# owl-digital-2.net
KiCad netlist of a schematic drawn in EAGLE
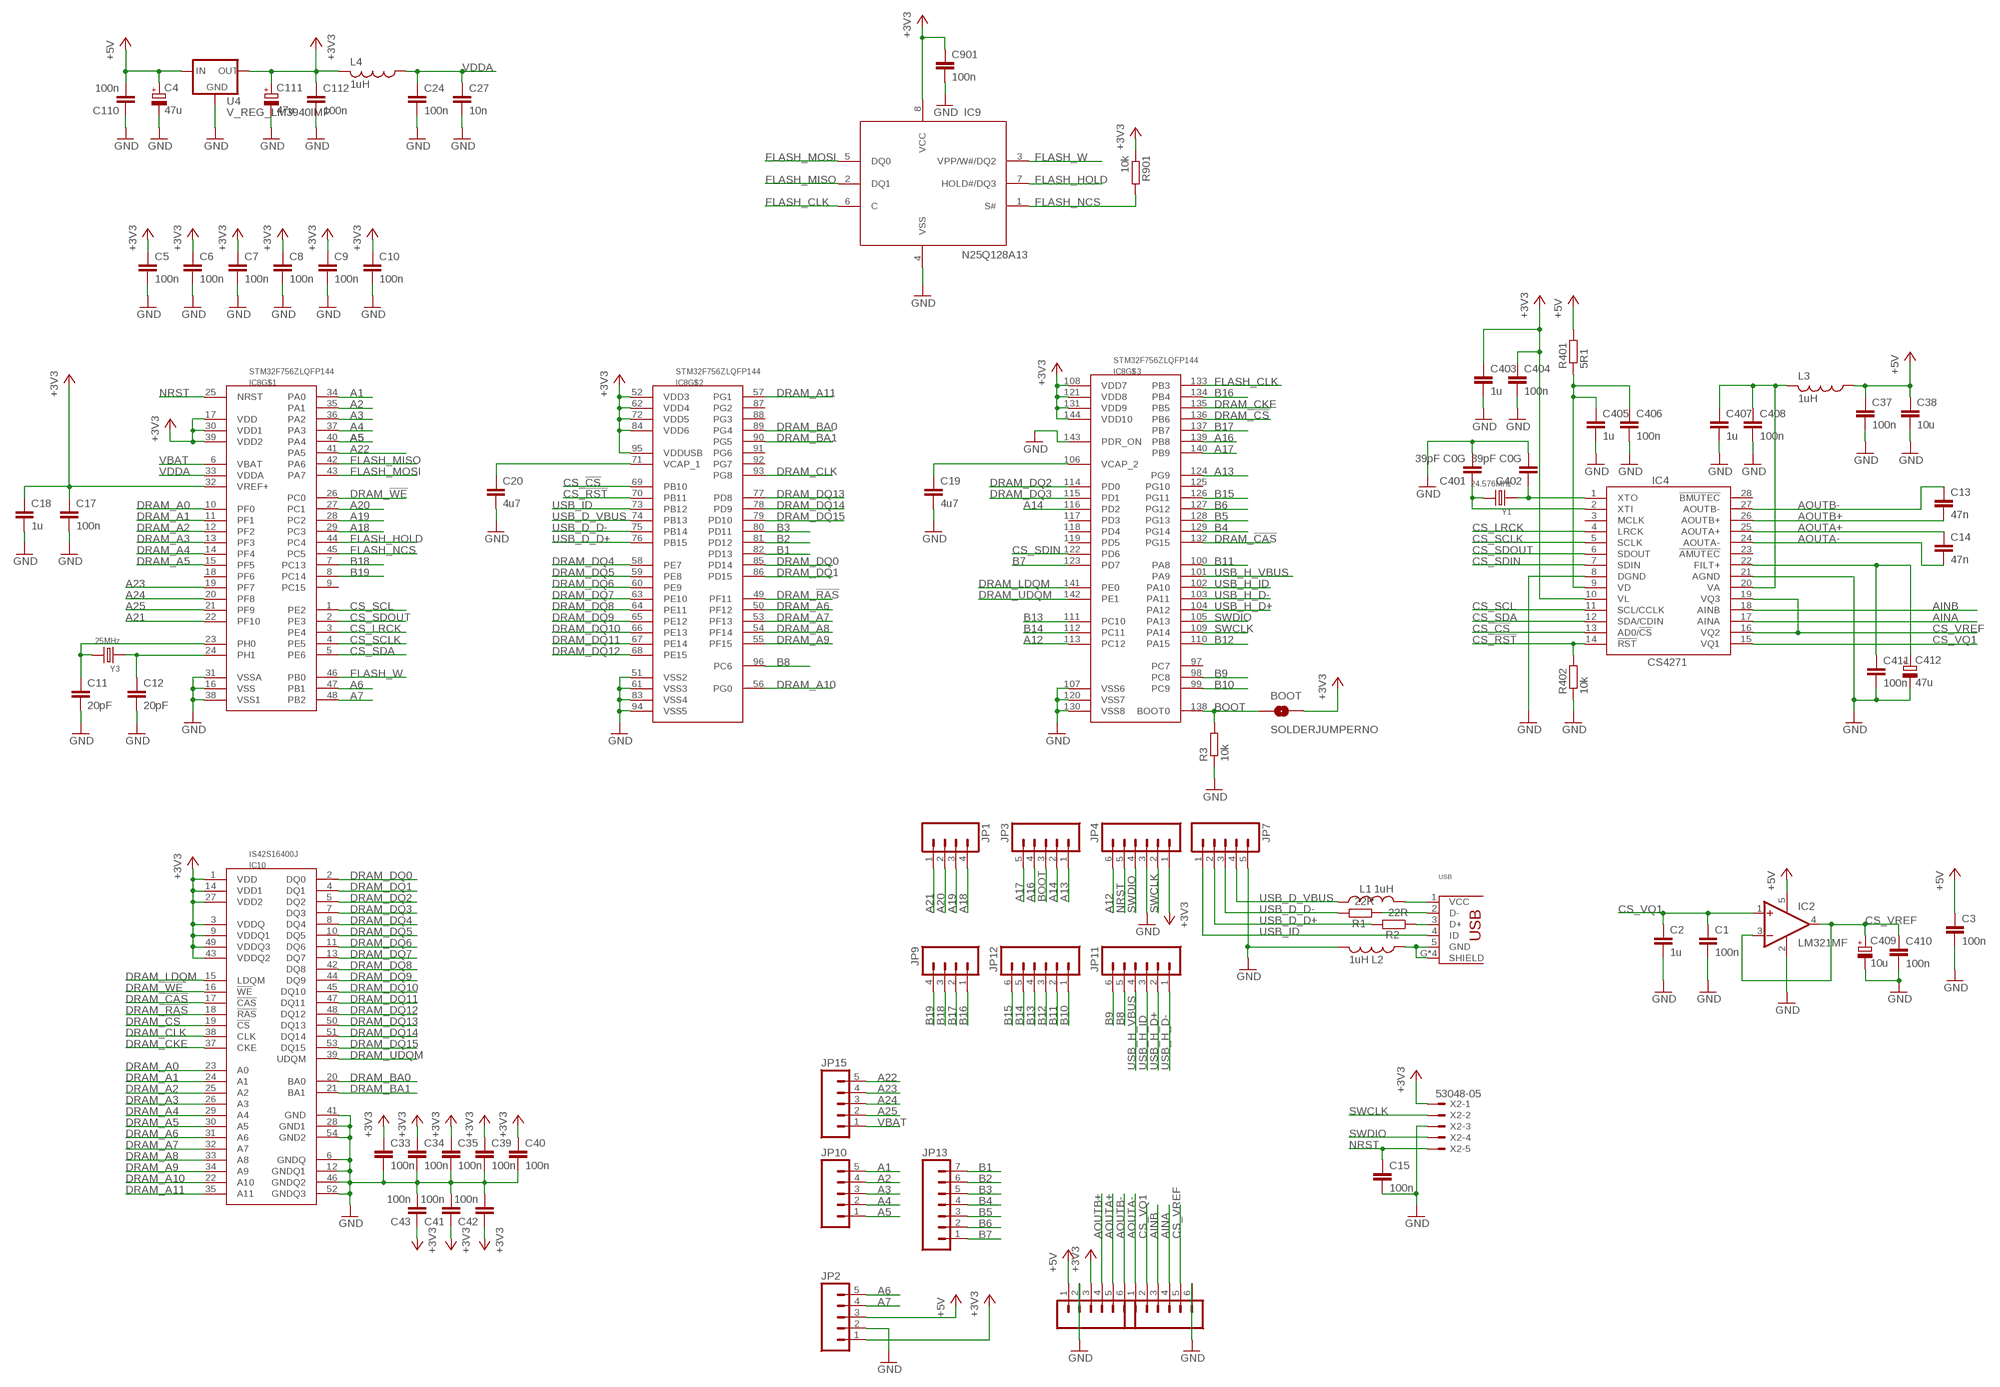
[diagram p0: schematic, sheet 1]

(export (version "E")
  (design (tool "Eeschema 10.0.6"))
  (components
    (comp (ref "BOOT")
      (value "SOLDERJUMPERNO")
      (footprint "eagle-import:SJ_2S-NO")
      (libsource (lib "eagle-import") (part "SOLDERJUMPERNO"))
    )
    (comp (ref "C1")
      (value "100n")
      (footprint "eagle-import:C0603")
      (libsource (lib "eagle-import") (part "C-EUC0603"))
    )
    (comp (ref "C2")
      (value "1u")
      (footprint "eagle-import:C0603")
      (libsource (lib "eagle-import") (part "C-EUC0603"))
    )
    (comp (ref "C3")
      (value "100n")
      (footprint "eagle-import:C0603")
      (libsource (lib "eagle-import") (part "C-EUC0603"))
    )
    (comp (ref "C4")
      (value "47u")
      (footprint "eagle-import:CPOL-5")
      (libsource (lib "eagle-import") (part "CPOL-EU153CLV-0505"))
    )
    (comp (ref "C5")
      (value "100n")
      (footprint "eagle-import:C0603")
      (libsource (lib "eagle-import") (part "C-EUC0603"))
    )
    (comp (ref "C6")
      (value "100n")
      (footprint "eagle-import:C0603")
      (libsource (lib "eagle-import") (part "C-EUC0603"))
    )
    (comp (ref "C7")
      (value "100n")
      (footprint "eagle-import:C0603")
      (libsource (lib "eagle-import") (part "C-EUC0603"))
    )
    (comp (ref "C8")
      (value "100n")
      (footprint "eagle-import:C0603")
      (libsource (lib "eagle-import") (part "C-EUC0603"))
    )
    (comp (ref "C9")
      (value "100n")
      (footprint "eagle-import:C0603")
      (libsource (lib "eagle-import") (part "C-EUC0603"))
    )
    (comp (ref "C10")
      (value "100n")
      (footprint "eagle-import:C0603")
      (libsource (lib "eagle-import") (part "C-EUC0603"))
    )
    (comp (ref "C11")
      (value "20pF")
      (footprint "eagle-import:C0603")
      (libsource (lib "eagle-import") (part "C-EUC0603"))
    )
    (comp (ref "C12")
      (value "20pF")
      (footprint "eagle-import:C0603")
      (libsource (lib "eagle-import") (part "C-EUC0603"))
    )
    (comp (ref "C13")
      (value "47n")
      (footprint "eagle-import:C0603")
      (libsource (lib "eagle-import") (part "C-EUC0603"))
    )
    (comp (ref "C14")
      (value "47n")
      (footprint "eagle-import:C0603")
      (libsource (lib "eagle-import") (part "C-EUC0603"))
    )
    (comp (ref "C15")
      (value "100n")
      (footprint "eagle-import:C0603")
      (libsource (lib "eagle-import") (part "C-EUC0603"))
    )
    (comp (ref "C17")
      (value "100n")
      (footprint "eagle-import:C0603")
      (libsource (lib "eagle-import") (part "C-EUC0603"))
    )
    (comp (ref "C18")
      (value "1u")
      (footprint "eagle-import:C0603")
      (libsource (lib "eagle-import") (part "C-EUC0603"))
    )
    (comp (ref "C19")
      (value "4u7")
      (footprint "eagle-import:C0603")
      (libsource (lib "eagle-import") (part "C-EUC0603"))
    )
    (comp (ref "C20")
      (value "4u7")
      (footprint "eagle-import:C0603")
      (libsource (lib "eagle-import") (part "C-EUC0603"))
    )
    (comp (ref "C24")
      (value "100n")
      (footprint "eagle-import:C0603")
      (libsource (lib "eagle-import") (part "C-EUC0603"))
    )
    (comp (ref "C27")
      (value "10n")
      (footprint "eagle-import:C0603")
      (libsource (lib "eagle-import") (part "C-EUC0603"))
    )
    (comp (ref "C33")
      (value "100n")
      (footprint "eagle-import:C0603")
      (libsource (lib "eagle-import") (part "C-EUC0603"))
    )
    (comp (ref "C34")
      (value "100n")
      (footprint "eagle-import:C0603")
      (libsource (lib "eagle-import") (part "C-EUC0603"))
    )
    (comp (ref "C35")
      (value "100n")
      (footprint "eagle-import:C0603")
      (libsource (lib "eagle-import") (part "C-EUC0603"))
    )
    (comp (ref "C37")
      (value "100n")
      (footprint "eagle-import:C0603")
      (libsource (lib "eagle-import") (part "C-EUC0603"))
    )
    (comp (ref "C38")
      (value "10u")
      (footprint "eagle-import:C1206")
      (libsource (lib "eagle-import") (part "C-EUC1206"))
    )
    (comp (ref "C39")
      (value "100n")
      (footprint "eagle-import:C0603")
      (libsource (lib "eagle-import") (part "C-EUC0603"))
    )
    (comp (ref "C40")
      (value "100n")
      (footprint "eagle-import:C0603")
      (libsource (lib "eagle-import") (part "C-EUC0603"))
    )
    (comp (ref "C41")
      (value "100n")
      (footprint "eagle-import:C0603")
      (libsource (lib "eagle-import") (part "C-EUC0603"))
    )
    (comp (ref "C42")
      (value "100n")
      (footprint "eagle-import:C0603")
      (libsource (lib "eagle-import") (part "C-EUC0603"))
    )
    (comp (ref "C43")
      (value "100n")
      (footprint "eagle-import:C0603")
      (libsource (lib "eagle-import") (part "C-EUC0603"))
    )
    (comp (ref "C110")
      (value "100n")
      (footprint "eagle-import:C0603")
      (libsource (lib "eagle-import") (part "C-EUC0603"))
    )
    (comp (ref "C111")
      (value "47u")
      (footprint "eagle-import:CPOL-5")
      (libsource (lib "eagle-import") (part "CPOL-EU153CLV-0505"))
    )
    (comp (ref "C112")
      (value "100n")
      (footprint "eagle-import:C0603")
      (libsource (lib "eagle-import") (part "C-EUC0603"))
    )
    (comp (ref "C401")
      (value "39pF C0G")
      (footprint "eagle-import:C0603")
      (libsource (lib "eagle-import") (part "C-EUC0603"))
    )
    (comp (ref "C402")
      (value "39pF C0G")
      (footprint "eagle-import:C0603")
      (libsource (lib "eagle-import") (part "C-EUC0603"))
    )
    (comp (ref "C403")
      (value "1u")
      (footprint "eagle-import:C0603")
      (libsource (lib "eagle-import") (part "C-EUC0603"))
    )
    (comp (ref "C404")
      (value "100n")
      (footprint "eagle-import:C0603")
      (libsource (lib "eagle-import") (part "C-EUC0603"))
    )
    (comp (ref "C405")
      (value "1u")
      (footprint "eagle-import:C0603")
      (libsource (lib "eagle-import") (part "C-EUC0603"))
    )
    (comp (ref "C406")
      (value "100n")
      (footprint "eagle-import:C0603")
      (libsource (lib "eagle-import") (part "C-EUC0603"))
    )
    (comp (ref "C407")
      (value "1u")
      (footprint "eagle-import:C0603")
      (libsource (lib "eagle-import") (part "C-EUC0603"))
    )
    (comp (ref "C408")
      (value "100n")
      (footprint "eagle-import:C0603")
      (libsource (lib "eagle-import") (part "C-EUC0603"))
    )
    (comp (ref "C409")
      (value "10u")
      (footprint "eagle-import:CPOL-5")
      (libsource (lib "eagle-import") (part "CPOL-EU153CLV-0505"))
    )
    (comp (ref "C410")
      (value "100n")
      (footprint "eagle-import:C0603")
      (libsource (lib "eagle-import") (part "C-EUC0603"))
    )
    (comp (ref "C411")
      (value "100n")
      (footprint "eagle-import:C0603")
      (libsource (lib "eagle-import") (part "C-EUC0603"))
    )
    (comp (ref "C412")
      (value "47u")
      (footprint "eagle-import:CPOL-5")
      (libsource (lib "eagle-import") (part "CPOL-EU153CLV-0505"))
    )
    (comp (ref "C901")
      (value "100n")
      (footprint "eagle-import:C0603")
      (libsource (lib "eagle-import") (part "C-EUC0603"))
    )
    (comp (ref "IC2")
      (value "LM321MF")
      (footprint "eagle-import:SOT23-5")
      (libsource (lib "eagle-import") (part "LM321?MF"))
    )
    (comp (ref "IC4")
      (value "CS4271")
      (footprint "eagle-import:TSSOP28-0.65-9.7X4.4MM")
      (libsource (lib "eagle-import") (part "CS4271"))
    )
    (comp (ref "IC8")
      (value "STM32F756ZLQFP144")
      (footprint "eagle-import:QFP50P2200X2200X160-144N")
      (fields (field (name "OC_FARNELL") "2484975"))
      (libsource (lib "eagle-import") (part "STM32F756ZLQFP144"))
    )
    (comp (ref "IC9")
      (value "N25Q128A13")
      (footprint "eagle-import:SO8W")
      (libsource (lib "eagle-import") (part "N25Q128A13"))
    )
    (comp (ref "IC10")
      (value "IS42S16400J")
      (footprint "eagle-import:TSOP54-400")
      (libsource (lib "eagle-import") (part "IS42S16400J"))
    )
    (comp (ref "JP1")
      (value "M04PTH")
      (footprint "eagle-import:1X04")
      (libsource (lib "eagle-import") (part "M04PTH"))
    )
    (comp (ref "JP2")
      (value "M05PTH")
      (footprint "eagle-import:1X05")
      (libsource (lib "eagle-import") (part "M05PTH"))
    )
    (comp (ref "JP3")
      (value "M05PTH")
      (footprint "eagle-import:1X05")
      (libsource (lib "eagle-import") (part "M05PTH"))
    )
    (comp (ref "JP4")
      (value "M06SIP")
      (footprint "eagle-import:1X06")
      (libsource (lib "eagle-import") (part "M06SIP"))
    )
    (comp (ref "JP5")
      (value "M06SIP")
      (footprint "eagle-import:1X06")
      (libsource (lib "eagle-import") (part "M06SIP"))
    )
    (comp (ref "JP6")
      (value "M06SIP")
      (footprint "eagle-import:1X06")
      (libsource (lib "eagle-import") (part "M06SIP"))
    )
    (comp (ref "JP7")
      (value "M05PTH")
      (footprint "eagle-import:1X05")
      (libsource (lib "eagle-import") (part "M05PTH"))
    )
    (comp (ref "JP9")
      (value "M04PTH")
      (footprint "eagle-import:1X04")
      (libsource (lib "eagle-import") (part "M04PTH"))
    )
    (comp (ref "JP10")
      (value "M05PTH")
      (footprint "eagle-import:1X05")
      (libsource (lib "eagle-import") (part "M05PTH"))
    )
    (comp (ref "JP11")
      (value "M06SIP")
      (footprint "eagle-import:1X06")
      (libsource (lib "eagle-import") (part "M06SIP"))
    )
    (comp (ref "JP12")
      (value "M06SIP")
      (footprint "eagle-import:1X06")
      (libsource (lib "eagle-import") (part "M06SIP"))
    )
    (comp (ref "JP13")
      (value "M07")
      (footprint "eagle-import:1X07")
      (libsource (lib "eagle-import") (part "M07"))
    )
    (comp (ref "JP15")
      (value "M05PTH")
      (footprint "eagle-import:1X05")
      (libsource (lib "eagle-import") (part "M05PTH"))
    )
    (comp (ref "L1")
      (value "1uH")
      (footprint "eagle-import:0603")
      (libsource (lib "eagle-import") (part "INDUCTOR"))
    )
    (comp (ref "L2")
      (value "1uH")
      (footprint "eagle-import:0603")
      (libsource (lib "eagle-import") (part "INDUCTOR"))
    )
    (comp (ref "L3")
      (value "1uH")
      (footprint "eagle-import:0603")
      (libsource (lib "eagle-import") (part "INDUCTOR"))
    )
    (comp (ref "L4")
      (value "1uH")
      (footprint "eagle-import:0603")
      (libsource (lib "eagle-import") (part "INDUCTOR"))
    )
    (comp (ref "R1")
      (value "22R")
      (footprint "eagle-import:0603")
      (libsource (lib "eagle-import") (part "R-EU_0603"))
    )
    (comp (ref "R2")
      (value "22R")
      (footprint "eagle-import:0603")
      (libsource (lib "eagle-import") (part "R-EU_0603"))
    )
    (comp (ref "R3")
      (value "10k")
      (footprint "eagle-import:0603")
      (libsource (lib "eagle-import") (part "R-EU_0603"))
    )
    (comp (ref "R401")
      (value "5R1")
      (footprint "eagle-import:0603")
      (libsource (lib "eagle-import") (part "R-EU_0603"))
    )
    (comp (ref "R402")
      (value "10k")
      (footprint "eagle-import:0603")
      (libsource (lib "eagle-import") (part "R-EU_0603"))
    )
    (comp (ref "R901")
      (value "10k")
      (footprint "eagle-import:0603")
      (libsource (lib "eagle-import") (part "R-EU_0603"))
    )
    (comp (ref "U4")
      (value "V_REG_LM3940IMP")
      (footprint "eagle-import:SOT223")
      (libsource (lib "eagle-import") (part "V_REG_LM3940IMP"))
    )
    (comp (ref "USB")
      (value "USB_HRS_ZX62-B-5PA(11)MICRO.B")
      (footprint "eagle-import:HRS_ZX62RD-AB-5P8")
      (libsource (lib "eagle-import") (part "USB_HRS_ZX62-B-5PA(11)MICRO.B"))
    )
    (comp (ref "X2")
      (value "53048-05")
      (footprint "eagle-import:53048-05")
      (fields (field (name "MF") "MOLEX") (field (name "MPN") "53048-0510"))
      (libsource (lib "eagle-import") (part "53?-05048"))
    )
    (comp (ref "Y1")
      (value "24.576MHz")
      (footprint "eagle-import:X2-SMD-5.0X3.2X1.3MM")
      (fields (field (name "MPN") "5032/2P"))
      (libsource (lib "eagle-import") (part "SMD-CRYSTAL-8MHZ-20PF-20PPM(2P-5.0X3.2MM)"))
    )
    (comp (ref "Y3")
      (value "25MHz")
      (footprint "eagle-import:X2-SMD-5.0X3.2X1.3MM")
      (fields (field (name "MPN") "5032/2P"))
      (libsource (lib "eagle-import") (part "SMD-CRYSTAL-8MHZ-20PF-20PPM(2P-5.0X3.2MM)"))
    )
  )
  (nets
    (net (code "1") (name "+3V3") (class "Default")
      (node (ref "BOOT") (pin "2") (pinfunction "2_2") (pintype "passive"))
      (node (ref "C10") (pin "1") (pinfunction "1_1") (pintype "passive"))
      (node (ref "C111") (pin "+") (pinfunction "+_+") (pintype "passive"))
      (node (ref "C112") (pin "1") (pinfunction "1_1") (pintype "passive"))
      (node (ref "C17") (pin "1") (pinfunction "1_1") (pintype "passive"))
      (node (ref "C18") (pin "1") (pinfunction "1_1") (pintype "passive"))
      (node (ref "C33") (pin "1") (pinfunction "1_1") (pintype "passive"))
      (node (ref "C34") (pin "1") (pinfunction "1_1") (pintype "passive"))
      (node (ref "C35") (pin "1") (pinfunction "1_1") (pintype "passive"))
      (node (ref "C39") (pin "1") (pinfunction "1_1") (pintype "passive"))
      (node (ref "C40") (pin "1") (pinfunction "1_1") (pintype "passive"))
      (node (ref "C403") (pin "1") (pinfunction "1_1") (pintype "passive"))
      (node (ref "C404") (pin "1") (pinfunction "1_1") (pintype "passive"))
      (node (ref "C41") (pin "1") (pinfunction "1_1") (pintype "passive"))
      (node (ref "C42") (pin "1") (pinfunction "1_1") (pintype "passive"))
      (node (ref "C43") (pin "1") (pinfunction "1_1") (pintype "passive"))
      (node (ref "C5") (pin "1") (pinfunction "1_1") (pintype "passive"))
      (node (ref "C6") (pin "1") (pinfunction "1_1") (pintype "passive"))
      (node (ref "C7") (pin "1") (pinfunction "1_1") (pintype "passive"))
      (node (ref "C8") (pin "1") (pinfunction "1_1") (pintype "passive"))
      (node (ref "C9") (pin "1") (pinfunction "1_1") (pintype "passive"))
      (node (ref "C901") (pin "1") (pinfunction "1_1") (pintype "passive"))
      (node (ref "IC10") (pin "1") (pinfunction "VDD_1") (pintype "bidirectional"))
      (node (ref "IC10") (pin "14") (pinfunction "VDD1_14") (pintype "bidirectional"))
      (node (ref "IC10") (pin "27") (pinfunction "VDD2_27") (pintype "bidirectional"))
      (node (ref "IC10") (pin "3") (pinfunction "VDDQ_3") (pintype "bidirectional"))
      (node (ref "IC10") (pin "43") (pinfunction "VDDQ2_43") (pintype "bidirectional"))
      (node (ref "IC10") (pin "49") (pinfunction "VDDQ3_49") (pintype "bidirectional"))
      (node (ref "IC10") (pin "9") (pinfunction "VDDQ1_9") (pintype "bidirectional"))
      (node (ref "IC4") (pin "10") (pinfunction "VL_10") (pintype "bidirectional"))
      (node (ref "IC8") (pin "108") (pinfunction "VDD7_108") (pintype "bidirectional"))
      (node (ref "IC8") (pin "121") (pinfunction "VDD8_121") (pintype "bidirectional"))
      (node (ref "IC8") (pin "131") (pinfunction "VDD9_131") (pintype "bidirectional"))
      (node (ref "IC8") (pin "144") (pinfunction "VDD10_144") (pintype "bidirectional"))
      (node (ref "IC8") (pin "17") (pinfunction "VDD_17") (pintype "bidirectional"))
      (node (ref "IC8") (pin "30") (pinfunction "VDD1_30") (pintype "bidirectional"))
      (node (ref "IC8") (pin "32") (pinfunction "VREF+_32") (pintype "bidirectional"))
      (node (ref "IC8") (pin "39") (pinfunction "VDD2_39") (pintype "bidirectional"))
      (node (ref "IC8") (pin "52") (pinfunction "VDD3_52") (pintype "bidirectional"))
      (node (ref "IC8") (pin "62") (pinfunction "VDD4_62") (pintype "bidirectional"))
      (node (ref "IC8") (pin "72") (pinfunction "VDD5_72") (pintype "bidirectional"))
      (node (ref "IC8") (pin "84") (pinfunction "VDD6_84") (pintype "bidirectional"))
      (node (ref "IC8") (pin "95") (pinfunction "VDDUSB_95") (pintype "bidirectional"))
      (node (ref "IC9") (pin "8") (pinfunction "VCC_8") (pintype "bidirectional"))
      (node (ref "JP2") (pin "1") (pinfunction "1_1") (pintype "passive"))
      (node (ref "JP4") (pin "1") (pinfunction "1_1") (pintype "passive"))
      (node (ref "JP5") (pin "3") (pinfunction "3_3") (pintype "passive"))
      (node (ref "L4") (pin "2") (pinfunction "2_2") (pintype "passive"))
      (node (ref "R901") (pin "1") (pinfunction "1_1") (pintype "passive"))
      (node (ref "U4") (pin "3") (pinfunction "OUT_3") (pintype "output"))
      (node (ref "X2") (pin "1") (pinfunction "S_1") (pintype "passive"))
    )
    (net (code "2") (name "+5V") (class "Default")
      (node (ref "C110") (pin "2") (pinfunction "2_2") (pintype "passive"))
      (node (ref "C3") (pin "1") (pinfunction "1_1") (pintype "passive"))
      (node (ref "C37") (pin "1") (pinfunction "1_1") (pintype "passive"))
      (node (ref "C38") (pin "1") (pinfunction "1_1") (pintype "passive"))
      (node (ref "C4") (pin "+") (pinfunction "+_+") (pintype "passive"))
      (node (ref "IC2") (pin "5") (pinfunction "V+_5") (pintype "power_in"))
      (node (ref "JP2") (pin "3") (pinfunction "3_3") (pintype "passive"))
      (node (ref "JP5") (pin "1") (pinfunction "1_1") (pintype "passive"))
      (node (ref "L3") (pin "1") (pinfunction "1_1") (pintype "passive"))
      (node (ref "R401") (pin "2") (pinfunction "2_2") (pintype "passive"))
      (node (ref "U4") (pin "1") (pinfunction "IN_1") (pintype "input"))
    )
    (net (code "3") (name "/A1") (class "Default")
      (node (ref "IC8") (pin "34") (pinfunction "PA0_34") (pintype "bidirectional"))
      (node (ref "JP10") (pin "5") (pinfunction "5_5") (pintype "passive"))
    )
    (net (code "4") (name "/A2") (class "Default")
      (node (ref "IC8") (pin "35") (pinfunction "PA1_35") (pintype "bidirectional"))
      (node (ref "JP10") (pin "4") (pinfunction "4_4") (pintype "passive"))
    )
    (net (code "5") (name "/A3") (class "Default")
      (node (ref "IC8") (pin "36") (pinfunction "PA2_36") (pintype "bidirectional"))
      (node (ref "JP10") (pin "3") (pinfunction "3_3") (pintype "passive"))
    )
    (net (code "6") (name "/A4") (class "Default")
      (node (ref "IC8") (pin "37") (pinfunction "PA3_37") (pintype "bidirectional"))
      (node (ref "JP10") (pin "2") (pinfunction "2_2") (pintype "passive"))
    )
    (net (code "7") (name "/A5") (class "Default")
      (node (ref "IC8") (pin "40") (pinfunction "PA4_40") (pintype "bidirectional"))
      (node (ref "JP10") (pin "1") (pinfunction "1_1") (pintype "passive"))
    )
    (net (code "8") (name "/A6") (class "Default")
      (node (ref "IC8") (pin "47") (pinfunction "PB1_47") (pintype "bidirectional"))
      (node (ref "JP2") (pin "5") (pinfunction "5_5") (pintype "passive"))
    )
    (net (code "9") (name "/A7") (class "Default")
      (node (ref "IC8") (pin "48") (pinfunction "PB2_48") (pintype "bidirectional"))
      (node (ref "JP2") (pin "4") (pinfunction "4_4") (pintype "passive"))
    )
    (net (code "10") (name "/A12") (class "Default")
      (node (ref "IC8") (pin "113") (pinfunction "PC12_113") (pintype "bidirectional"))
      (node (ref "JP4") (pin "6") (pinfunction "6_6") (pintype "passive"))
    )
    (net (code "11") (name "/A13") (class "Default")
      (node (ref "IC8") (pin "124") (pinfunction "PG9_124") (pintype "bidirectional"))
      (node (ref "JP3") (pin "1") (pinfunction "1_1") (pintype "passive"))
    )
    (net (code "12") (name "/A14") (class "Default")
      (node (ref "IC8") (pin "116") (pinfunction "PD2_116") (pintype "bidirectional"))
      (node (ref "JP3") (pin "2") (pinfunction "2_2") (pintype "passive"))
    )
    (net (code "13") (name "/A16") (class "Default")
      (node (ref "IC8") (pin "139") (pinfunction "PB8_139") (pintype "bidirectional"))
      (node (ref "JP3") (pin "4") (pinfunction "4_4") (pintype "passive"))
    )
    (net (code "14") (name "/A17") (class "Default")
      (node (ref "IC8") (pin "140") (pinfunction "PB9_140") (pintype "bidirectional"))
      (node (ref "JP3") (pin "5") (pinfunction "5_5") (pintype "passive"))
    )
    (net (code "15") (name "/A18") (class "Default")
      (node (ref "IC8") (pin "29") (pinfunction "PC3_29") (pintype "bidirectional"))
      (node (ref "JP1") (pin "4") (pinfunction "4_4") (pintype "passive"))
    )
    (net (code "16") (name "/A19") (class "Default")
      (node (ref "IC8") (pin "28") (pinfunction "PC2_28") (pintype "bidirectional"))
      (node (ref "JP1") (pin "3") (pinfunction "3_3") (pintype "passive"))
    )
    (net (code "17") (name "/A20") (class "Default")
      (node (ref "IC8") (pin "27") (pinfunction "PC1_27") (pintype "bidirectional"))
      (node (ref "JP1") (pin "2") (pinfunction "2_2") (pintype "passive"))
    )
    (net (code "18") (name "/A21") (class "Default")
      (node (ref "IC8") (pin "22") (pinfunction "PF10_22") (pintype "bidirectional"))
      (node (ref "JP1") (pin "1") (pinfunction "1_1") (pintype "passive"))
    )
    (net (code "19") (name "/A22") (class "Default")
      (node (ref "IC8") (pin "41") (pinfunction "PA5_41") (pintype "bidirectional"))
      (node (ref "JP15") (pin "5") (pinfunction "5_5") (pintype "passive"))
    )
    (net (code "20") (name "/A23") (class "Default")
      (node (ref "IC8") (pin "19") (pinfunction "PF7_19") (pintype "bidirectional"))
      (node (ref "JP15") (pin "4") (pinfunction "4_4") (pintype "passive"))
    )
    (net (code "21") (name "/A24") (class "Default")
      (node (ref "IC8") (pin "20") (pinfunction "PF8_20") (pintype "bidirectional"))
      (node (ref "JP15") (pin "3") (pinfunction "3_3") (pintype "passive"))
    )
    (net (code "22") (name "/A25") (class "Default")
      (node (ref "IC8") (pin "21") (pinfunction "PF9_21") (pintype "bidirectional"))
      (node (ref "JP15") (pin "2") (pinfunction "2_2") (pintype "passive"))
    )
    (net (code "23") (name "/AINA") (class "Default")
      (node (ref "IC4") (pin "17") (pinfunction "AINA_17") (pintype "bidirectional"))
      (node (ref "JP6") (pin "4") (pinfunction "4_4") (pintype "passive"))
    )
    (net (code "24") (name "/AINB") (class "Default")
      (node (ref "IC4") (pin "18") (pinfunction "AINB_18") (pintype "bidirectional"))
      (node (ref "JP6") (pin "3") (pinfunction "3_3") (pintype "passive"))
    )
    (net (code "25") (name "/AOUTA+") (class "Default")
      (node (ref "C14") (pin "1") (pinfunction "1_1") (pintype "passive"))
      (node (ref "IC4") (pin "25") (pinfunction "AOUTA+_25") (pintype "bidirectional"))
      (node (ref "JP5") (pin "5") (pinfunction "5_5") (pintype "passive"))
    )
    (net (code "26") (name "/AOUTA-") (class "Default")
      (node (ref "C14") (pin "2") (pinfunction "2_2") (pintype "passive"))
      (node (ref "IC4") (pin "24") (pinfunction "AOUTA-_24") (pintype "bidirectional"))
      (node (ref "JP6") (pin "1") (pinfunction "1_1") (pintype "passive"))
    )
    (net (code "27") (name "/AOUTB+") (class "Default")
      (node (ref "C13") (pin "2") (pinfunction "2_2") (pintype "passive"))
      (node (ref "IC4") (pin "26") (pinfunction "AOUTB+_26") (pintype "bidirectional"))
      (node (ref "JP5") (pin "4") (pinfunction "4_4") (pintype "passive"))
    )
    (net (code "28") (name "/AOUTB-") (class "Default")
      (node (ref "C13") (pin "1") (pinfunction "1_1") (pintype "passive"))
      (node (ref "IC4") (pin "27") (pinfunction "AOUTB-_27") (pintype "bidirectional"))
      (node (ref "JP5") (pin "6") (pinfunction "6_6") (pintype "passive"))
    )
    (net (code "29") (name "/B1") (class "Default")
      (node (ref "IC8") (pin "82") (pinfunction "PD13_82") (pintype "bidirectional"))
      (node (ref "JP13") (pin "7") (pinfunction "7_7") (pintype "passive"))
    )
    (net (code "30") (name "/B2") (class "Default")
      (node (ref "IC8") (pin "81") (pinfunction "PD12_81") (pintype "bidirectional"))
      (node (ref "JP13") (pin "6") (pinfunction "6_6") (pintype "passive"))
    )
    (net (code "31") (name "/B3") (class "Default")
      (node (ref "IC8") (pin "80") (pinfunction "PD11_80") (pintype "bidirectional"))
      (node (ref "JP13") (pin "5") (pinfunction "5_5") (pintype "passive"))
    )
    (net (code "32") (name "/B4") (class "Default")
      (node (ref "IC8") (pin "129") (pinfunction "PG14_129") (pintype "bidirectional"))
      (node (ref "JP13") (pin "4") (pinfunction "4_4") (pintype "passive"))
    )
    (net (code "33") (name "/B5") (class "Default")
      (node (ref "IC8") (pin "128") (pinfunction "PG13_128") (pintype "bidirectional"))
      (node (ref "JP13") (pin "3") (pinfunction "3_3") (pintype "passive"))
    )
    (net (code "34") (name "/B6") (class "Default")
      (node (ref "IC8") (pin "127") (pinfunction "PG12_127") (pintype "bidirectional"))
      (node (ref "JP13") (pin "2") (pinfunction "2_2") (pintype "passive"))
    )
    (net (code "35") (name "/B7") (class "Default")
      (node (ref "IC8") (pin "123") (pinfunction "PD7_123") (pintype "bidirectional"))
      (node (ref "JP13") (pin "1") (pinfunction "1_1") (pintype "passive"))
    )
    (net (code "36") (name "/B8") (class "Default")
      (node (ref "IC8") (pin "96") (pinfunction "PC6_96") (pintype "bidirectional"))
      (node (ref "JP11") (pin "5") (pinfunction "5_5") (pintype "passive"))
    )
    (net (code "37") (name "/B9") (class "Default")
      (node (ref "IC8") (pin "98") (pinfunction "PC8_98") (pintype "bidirectional"))
      (node (ref "JP11") (pin "6") (pinfunction "6_6") (pintype "passive"))
    )
    (net (code "38") (name "/B10") (class "Default")
      (node (ref "IC8") (pin "99") (pinfunction "PC9_99") (pintype "bidirectional"))
      (node (ref "JP12") (pin "1") (pinfunction "1_1") (pintype "passive"))
    )
    (net (code "39") (name "/B11") (class "Default")
      (node (ref "IC8") (pin "100") (pinfunction "PA8_100") (pintype "bidirectional"))
      (node (ref "JP12") (pin "2") (pinfunction "2_2") (pintype "passive"))
    )
    (net (code "40") (name "/B12") (class "Default")
      (node (ref "IC8") (pin "110") (pinfunction "PA15_110") (pintype "bidirectional"))
      (node (ref "JP12") (pin "3") (pinfunction "3_3") (pintype "passive"))
    )
    (net (code "41") (name "/B13") (class "Default")
      (node (ref "IC8") (pin "111") (pinfunction "PC10_111") (pintype "bidirectional"))
      (node (ref "JP12") (pin "4") (pinfunction "4_4") (pintype "passive"))
    )
    (net (code "42") (name "/B14") (class "Default")
      (node (ref "IC8") (pin "112") (pinfunction "PC11_112") (pintype "bidirectional"))
      (node (ref "JP12") (pin "5") (pinfunction "5_5") (pintype "passive"))
    )
    (net (code "43") (name "/B15") (class "Default")
      (node (ref "IC8") (pin "126") (pinfunction "PG11_126") (pintype "bidirectional"))
      (node (ref "JP12") (pin "6") (pinfunction "6_6") (pintype "passive"))
    )
    (net (code "44") (name "/B16") (class "Default")
      (node (ref "IC8") (pin "134") (pinfunction "PB4_134") (pintype "bidirectional"))
      (node (ref "JP9") (pin "1") (pinfunction "1_1") (pintype "passive"))
    )
    (net (code "45") (name "/B17") (class "Default")
      (node (ref "IC8") (pin "137") (pinfunction "PB7_137") (pintype "bidirectional"))
      (node (ref "JP9") (pin "2") (pinfunction "2_2") (pintype "passive"))
    )
    (net (code "46") (name "/B18") (class "Default")
      (node (ref "IC8") (pin "7") (pinfunction "PC13_7") (pintype "bidirectional"))
      (node (ref "JP9") (pin "3") (pinfunction "3_3") (pintype "passive"))
    )
    (net (code "47") (name "/B19") (class "Default")
      (node (ref "IC8") (pin "8") (pinfunction "PC14_8") (pintype "bidirectional"))
      (node (ref "JP9") (pin "4") (pinfunction "4_4") (pintype "passive"))
    )
    (net (code "48") (name "/BOOT") (class "Default")
      (node (ref "BOOT") (pin "1") (pinfunction "1_1") (pintype "passive"))
      (node (ref "IC8") (pin "138") (pinfunction "BOOT0_138") (pintype "bidirectional"))
      (node (ref "JP3") (pin "3") (pinfunction "3_3") (pintype "passive"))
      (node (ref "R3") (pin "2") (pinfunction "2_2") (pintype "passive"))
    )
    (net (code "49") (name "/CS_LRCK") (class "Default")
      (node (ref "IC4") (pin "4") (pinfunction "LRCK_4") (pintype "bidirectional"))
      (node (ref "IC8") (pin "3") (pinfunction "PE4_3") (pintype "bidirectional"))
    )
    (net (code "50") (name "/CS_SCL") (class "Default")
      (node (ref "IC4") (pin "11") (pinfunction "SCL/CCLK_11") (pintype "bidirectional"))
      (node (ref "IC8") (pin "1") (pinfunction "PE2_1") (pintype "bidirectional"))
    )
    (net (code "51") (name "/CS_SCLK") (class "Default")
      (node (ref "IC4") (pin "5") (pinfunction "SCLK_5") (pintype "bidirectional"))
      (node (ref "IC8") (pin "4") (pinfunction "PE5_4") (pintype "bidirectional"))
    )
    (net (code "52") (name "/CS_SDA") (class "Default")
      (node (ref "IC4") (pin "12") (pinfunction "SDA/CDIN_12") (pintype "bidirectional"))
      (node (ref "IC8") (pin "5") (pinfunction "PE6_5") (pintype "bidirectional"))
    )
    (net (code "53") (name "/CS_SDIN") (class "Default")
      (node (ref "IC4") (pin "7") (pinfunction "SDIN_7") (pintype "bidirectional"))
      (node (ref "IC8") (pin "122") (pinfunction "PD6_122") (pintype "bidirectional"))
    )
    (net (code "54") (name "/CS_SDOUT") (class "Default")
      (node (ref "IC4") (pin "6") (pinfunction "SDOUT_6") (pintype "bidirectional"))
      (node (ref "IC8") (pin "2") (pinfunction "PE3_2") (pintype "bidirectional"))
    )
    (net (code "55") (name "/CS_VQ1") (class "Default")
      (node (ref "C1") (pin "1") (pinfunction "1_1") (pintype "passive"))
      (node (ref "C2") (pin "1") (pinfunction "1_1") (pintype "passive"))
      (node (ref "IC2") (pin "1") (pinfunction "+IN_1") (pintype "input"))
      (node (ref "IC4") (pin "15") (pinfunction "VQ1_15") (pintype "bidirectional"))
      (node (ref "JP6") (pin "2") (pinfunction "2_2") (pintype "passive"))
    )
    (net (code "56") (name "/CS_VREF") (class "Default")
      (node (ref "C409") (pin "+") (pinfunction "+_+") (pintype "passive"))
      (node (ref "C410") (pin "1") (pinfunction "1_1") (pintype "passive"))
      (node (ref "IC2") (pin "3") (pinfunction "-IN_3") (pintype "input"))
      (node (ref "IC2") (pin "4") (pinfunction "OUT_4") (pintype "output"))
      (node (ref "IC4") (pin "16") (pinfunction "VQ2_16") (pintype "bidirectional"))
      (node (ref "IC4") (pin "19") (pinfunction "VQ3_19") (pintype "bidirectional"))
      (node (ref "JP6") (pin "5") (pinfunction "5_5") (pintype "passive"))
    )
    (net (code "57") (name "/CS_~{CS}") (class "Default")
      (node (ref "IC4") (pin "13") (pinfunction "AD0/~{CS}_13") (pintype "bidirectional"))
      (node (ref "IC8") (pin "69") (pinfunction "PB10_69") (pintype "bidirectional"))
    )
    (net (code "58") (name "/CS_~{RST}") (class "Default")
      (node (ref "IC4") (pin "14") (pinfunction "~{RST}_14") (pintype "bidirectional"))
      (node (ref "IC8") (pin "70") (pinfunction "PB11_70") (pintype "bidirectional"))
      (node (ref "R402") (pin "2") (pinfunction "2_2") (pintype "passive"))
    )
    (net (code "59") (name "/DRAM_A0") (class "Default")
      (node (ref "IC10") (pin "23") (pinfunction "A0_23") (pintype "bidirectional"))
      (node (ref "IC8") (pin "10") (pinfunction "PF0_10") (pintype "bidirectional"))
    )
    (net (code "60") (name "/DRAM_A1") (class "Default")
      (node (ref "IC10") (pin "24") (pinfunction "A1_24") (pintype "bidirectional"))
      (node (ref "IC8") (pin "11") (pinfunction "PF1_11") (pintype "bidirectional"))
    )
    (net (code "61") (name "/DRAM_A2") (class "Default")
      (node (ref "IC10") (pin "25") (pinfunction "A2_25") (pintype "bidirectional"))
      (node (ref "IC8") (pin "12") (pinfunction "PF2_12") (pintype "bidirectional"))
    )
    (net (code "62") (name "/DRAM_A3") (class "Default")
      (node (ref "IC10") (pin "26") (pinfunction "A3_26") (pintype "bidirectional"))
      (node (ref "IC8") (pin "13") (pinfunction "PF3_13") (pintype "bidirectional"))
    )
    (net (code "63") (name "/DRAM_A4") (class "Default")
      (node (ref "IC10") (pin "29") (pinfunction "A4_29") (pintype "bidirectional"))
      (node (ref "IC8") (pin "14") (pinfunction "PF4_14") (pintype "bidirectional"))
    )
    (net (code "64") (name "/DRAM_A5") (class "Default")
      (node (ref "IC10") (pin "30") (pinfunction "A5_30") (pintype "bidirectional"))
      (node (ref "IC8") (pin "15") (pinfunction "PF5_15") (pintype "bidirectional"))
    )
    (net (code "65") (name "/DRAM_A6") (class "Default")
      (node (ref "IC10") (pin "31") (pinfunction "A6_31") (pintype "bidirectional"))
      (node (ref "IC8") (pin "50") (pinfunction "PF12_50") (pintype "bidirectional"))
    )
    (net (code "66") (name "/DRAM_A7") (class "Default")
      (node (ref "IC10") (pin "32") (pinfunction "A7_32") (pintype "bidirectional"))
      (node (ref "IC8") (pin "53") (pinfunction "PF13_53") (pintype "bidirectional"))
    )
    (net (code "67") (name "/DRAM_A8") (class "Default")
      (node (ref "IC10") (pin "33") (pinfunction "A8_33") (pintype "bidirectional"))
      (node (ref "IC8") (pin "54") (pinfunction "PF14_54") (pintype "bidirectional"))
    )
    (net (code "68") (name "/DRAM_A9") (class "Default")
      (node (ref "IC10") (pin "34") (pinfunction "A9_34") (pintype "bidirectional"))
      (node (ref "IC8") (pin "55") (pinfunction "PF15_55") (pintype "bidirectional"))
    )
    (net (code "69") (name "/DRAM_A10") (class "Default")
      (node (ref "IC10") (pin "22") (pinfunction "A10_22") (pintype "bidirectional"))
      (node (ref "IC8") (pin "56") (pinfunction "PG0_56") (pintype "bidirectional"))
    )
    (net (code "70") (name "/DRAM_A11") (class "Default")
      (node (ref "IC10") (pin "35") (pinfunction "A11_35") (pintype "bidirectional"))
      (node (ref "IC8") (pin "57") (pinfunction "PG1_57") (pintype "bidirectional"))
    )
    (net (code "71") (name "/DRAM_BA0") (class "Default")
      (node (ref "IC10") (pin "20") (pinfunction "BA0_20") (pintype "bidirectional"))
      (node (ref "IC8") (pin "89") (pinfunction "PG4_89") (pintype "bidirectional"))
    )
    (net (code "72") (name "/DRAM_BA1") (class "Default")
      (node (ref "IC10") (pin "21") (pinfunction "BA1_21") (pintype "bidirectional"))
      (node (ref "IC8") (pin "90") (pinfunction "PG5_90") (pintype "bidirectional"))
    )
    (net (code "73") (name "/DRAM_CKE") (class "Default")
      (node (ref "IC10") (pin "37") (pinfunction "CKE_37") (pintype "bidirectional"))
      (node (ref "IC8") (pin "135") (pinfunction "PB5_135") (pintype "bidirectional"))
    )
    (net (code "74") (name "/DRAM_CLK") (class "Default")
      (node (ref "IC10") (pin "38") (pinfunction "CLK_38") (pintype "bidirectional"))
      (node (ref "IC8") (pin "93") (pinfunction "PG8_93") (pintype "bidirectional"))
    )
    (net (code "75") (name "/DRAM_DQ0") (class "Default")
      (node (ref "IC10") (pin "2") (pinfunction "DQ0_2") (pintype "bidirectional"))
      (node (ref "IC8") (pin "85") (pinfunction "PD14_85") (pintype "bidirectional"))
    )
    (net (code "76") (name "/DRAM_DQ1") (class "Default")
      (node (ref "IC10") (pin "4") (pinfunction "DQ1_4") (pintype "bidirectional"))
      (node (ref "IC8") (pin "86") (pinfunction "PD15_86") (pintype "bidirectional"))
    )
    (net (code "77") (name "/DRAM_DQ2") (class "Default")
      (node (ref "IC10") (pin "5") (pinfunction "DQ2_5") (pintype "bidirectional"))
      (node (ref "IC8") (pin "114") (pinfunction "PD0_114") (pintype "bidirectional"))
    )
    (net (code "78") (name "/DRAM_DQ3") (class "Default")
      (node (ref "IC10") (pin "7") (pinfunction "DQ3_7") (pintype "bidirectional"))
      (node (ref "IC8") (pin "115") (pinfunction "PD1_115") (pintype "bidirectional"))
    )
    (net (code "79") (name "/DRAM_DQ4") (class "Default")
      (node (ref "IC10") (pin "8") (pinfunction "DQ4_8") (pintype "bidirectional"))
      (node (ref "IC8") (pin "58") (pinfunction "PE7_58") (pintype "bidirectional"))
    )
    (net (code "80") (name "/DRAM_DQ5") (class "Default")
      (node (ref "IC10") (pin "10") (pinfunction "DQ5_10") (pintype "bidirectional"))
      (node (ref "IC8") (pin "59") (pinfunction "PE8_59") (pintype "bidirectional"))
    )
    (net (code "81") (name "/DRAM_DQ6") (class "Default")
      (node (ref "IC10") (pin "11") (pinfunction "DQ6_11") (pintype "bidirectional"))
      (node (ref "IC8") (pin "60") (pinfunction "PE9_60") (pintype "bidirectional"))
    )
    (net (code "82") (name "/DRAM_DQ7") (class "Default")
      (node (ref "IC10") (pin "13") (pinfunction "DQ7_13") (pintype "bidirectional"))
      (node (ref "IC8") (pin "63") (pinfunction "PE10_63") (pintype "bidirectional"))
    )
    (net (code "83") (name "/DRAM_DQ8") (class "Default")
      (node (ref "IC10") (pin "42") (pinfunction "DQ8_42") (pintype "bidirectional"))
      (node (ref "IC8") (pin "64") (pinfunction "PE11_64") (pintype "bidirectional"))
    )
    (net (code "84") (name "/DRAM_DQ9") (class "Default")
      (node (ref "IC10") (pin "44") (pinfunction "DQ9_44") (pintype "bidirectional"))
      (node (ref "IC8") (pin "65") (pinfunction "PE12_65") (pintype "bidirectional"))
    )
    (net (code "85") (name "/DRAM_DQ10") (class "Default")
      (node (ref "IC10") (pin "45") (pinfunction "DQ10_45") (pintype "bidirectional"))
      (node (ref "IC8") (pin "66") (pinfunction "PE13_66") (pintype "bidirectional"))
    )
    (net (code "86") (name "/DRAM_DQ11") (class "Default")
      (node (ref "IC10") (pin "47") (pinfunction "DQ11_47") (pintype "bidirectional"))
      (node (ref "IC8") (pin "67") (pinfunction "PE14_67") (pintype "bidirectional"))
    )
    (net (code "87") (name "/DRAM_DQ12") (class "Default")
      (node (ref "IC10") (pin "48") (pinfunction "DQ12_48") (pintype "bidirectional"))
      (node (ref "IC8") (pin "68") (pinfunction "PE15_68") (pintype "bidirectional"))
    )
    (net (code "88") (name "/DRAM_DQ13") (class "Default")
      (node (ref "IC10") (pin "50") (pinfunction "DQ13_50") (pintype "bidirectional"))
      (node (ref "IC8") (pin "77") (pinfunction "PD8_77") (pintype "bidirectional"))
    )
    (net (code "89") (name "/DRAM_DQ14") (class "Default")
      (node (ref "IC10") (pin "51") (pinfunction "DQ14_51") (pintype "bidirectional"))
      (node (ref "IC8") (pin "78") (pinfunction "PD9_78") (pintype "bidirectional"))
    )
    (net (code "90") (name "/DRAM_DQ15") (class "Default")
      (node (ref "IC10") (pin "53") (pinfunction "DQ15_53") (pintype "bidirectional"))
      (node (ref "IC8") (pin "79") (pinfunction "PD10_79") (pintype "bidirectional"))
    )
    (net (code "91") (name "/DRAM_LDQM") (class "Default")
      (node (ref "IC10") (pin "15") (pinfunction "LDQM_15") (pintype "bidirectional"))
      (node (ref "IC8") (pin "141") (pinfunction "PE0_141") (pintype "bidirectional"))
    )
    (net (code "92") (name "/DRAM_UDQM") (class "Default")
      (node (ref "IC10") (pin "39") (pinfunction "UDQM_39") (pintype "bidirectional"))
      (node (ref "IC8") (pin "142") (pinfunction "PE1_142") (pintype "bidirectional"))
    )
    (net (code "93") (name "/DRAM_~{CAS}") (class "Default")
      (node (ref "IC10") (pin "17") (pinfunction "~{CAS}_17") (pintype "bidirectional"))
      (node (ref "IC8") (pin "132") (pinfunction "PG15_132") (pintype "bidirectional"))
    )
    (net (code "94") (name "/DRAM_~{CS}") (class "Default")
      (node (ref "IC10") (pin "19") (pinfunction "~{CS}_19") (pintype "bidirectional"))
      (node (ref "IC8") (pin "136") (pinfunction "PB6_136") (pintype "bidirectional"))
    )
    (net (code "95") (name "/DRAM_~{RAS}") (class "Default")
      (node (ref "IC10") (pin "18") (pinfunction "~{RAS}_18") (pintype "bidirectional"))
      (node (ref "IC8") (pin "49") (pinfunction "PF11_49") (pintype "bidirectional"))
    )
    (net (code "96") (name "/DRAM_~{WE}") (class "Default")
      (node (ref "IC10") (pin "16") (pinfunction "~{WE}_16") (pintype "bidirectional"))
      (node (ref "IC8") (pin "26") (pinfunction "PC0_26") (pintype "bidirectional"))
    )
    (net (code "97") (name "/FLASH_CLK") (class "Default")
      (node (ref "IC8") (pin "133") (pinfunction "PB3_133") (pintype "bidirectional"))
      (node (ref "IC9") (pin "6") (pinfunction "C_6") (pintype "bidirectional"))
    )
    (net (code "98") (name "/FLASH_HOLD") (class "Default")
      (node (ref "IC8") (pin "44") (pinfunction "PC4_44") (pintype "bidirectional"))
      (node (ref "IC9") (pin "7") (pinfunction "HOLD#/DQ3_7") (pintype "bidirectional"))
    )
    (net (code "99") (name "/FLASH_MISO") (class "Default")
      (node (ref "IC8") (pin "42") (pinfunction "PA6_42") (pintype "bidirectional"))
      (node (ref "IC9") (pin "2") (pinfunction "DQ1_2") (pintype "bidirectional"))
    )
    (net (code "100") (name "/FLASH_MOSI") (class "Default")
      (node (ref "IC8") (pin "43") (pinfunction "PA7_43") (pintype "bidirectional"))
      (node (ref "IC9") (pin "5") (pinfunction "DQ0_5") (pintype "bidirectional"))
    )
    (net (code "101") (name "/FLASH_NCS") (class "Default")
      (node (ref "IC8") (pin "45") (pinfunction "PC5_45") (pintype "bidirectional"))
      (node (ref "IC9") (pin "1") (pinfunction "S#_1") (pintype "bidirectional"))
      (node (ref "R901") (pin "2") (pinfunction "2_2") (pintype "passive"))
    )
    (net (code "102") (name "/FLASH_W") (class "Default")
      (node (ref "IC8") (pin "46") (pinfunction "PB0_46") (pintype "bidirectional"))
      (node (ref "IC9") (pin "3") (pinfunction "VPP/W#/DQ2_3") (pintype "bidirectional"))
    )
    (net (code "103") (name "/NRST") (class "Default")
      (node (ref "C15") (pin "1") (pinfunction "1_1") (pintype "passive"))
      (node (ref "IC8") (pin "25") (pinfunction "NRST_25") (pintype "bidirectional"))
      (node (ref "JP4") (pin "5") (pinfunction "5_5") (pintype "passive"))
      (node (ref "X2") (pin "5") (pinfunction "S_5") (pintype "passive"))
    )
    (net (code "104") (name "/SWCLK") (class "Default")
      (node (ref "IC8") (pin "109") (pinfunction "PA14_109") (pintype "bidirectional"))
      (node (ref "JP4") (pin "2") (pinfunction "2_2") (pintype "passive"))
      (node (ref "X2") (pin "2") (pinfunction "S_2") (pintype "passive"))
    )
    (net (code "105") (name "/SWDIO") (class "Default")
      (node (ref "IC8") (pin "105") (pinfunction "PA13_105") (pintype "bidirectional"))
      (node (ref "JP4") (pin "4") (pinfunction "4_4") (pintype "passive"))
      (node (ref "X2") (pin "4") (pinfunction "S_4") (pintype "passive"))
    )
    (net (code "106") (name "/USB_D_D+") (class "Default")
      (node (ref "IC8") (pin "76") (pinfunction "PB15_76") (pintype "bidirectional"))
      (node (ref "JP7") (pin "2") (pinfunction "2_2") (pintype "passive"))
      (node (ref "R2") (pin "2") (pinfunction "2_2") (pintype "passive"))
    )
    (net (code "107") (name "/USB_D_D-") (class "Default")
      (node (ref "IC8") (pin "75") (pinfunction "PB14_75") (pintype "bidirectional"))
      (node (ref "JP7") (pin "3") (pinfunction "3_3") (pintype "passive"))
      (node (ref "R1") (pin "2") (pinfunction "2_2") (pintype "passive"))
    )
    (net (code "108") (name "/USB_D_VBUS") (class "Default")
      (node (ref "IC8") (pin "74") (pinfunction "PB13_74") (pintype "bidirectional"))
      (node (ref "JP7") (pin "4") (pinfunction "4_4") (pintype "passive"))
      (node (ref "L1") (pin "1") (pinfunction "1_1") (pintype "passive"))
    )
    (net (code "109") (name "/USB_H_D+") (class "Default")
      (node (ref "IC8") (pin "104") (pinfunction "PA12_104") (pintype "bidirectional"))
      (node (ref "JP11") (pin "2") (pinfunction "2_2") (pintype "passive"))
    )
    (net (code "110") (name "/USB_H_D-") (class "Default")
      (node (ref "IC8") (pin "103") (pinfunction "PA11_103") (pintype "bidirectional"))
      (node (ref "JP11") (pin "1") (pinfunction "1_1") (pintype "passive"))
    )
    (net (code "111") (name "/USB_H_ID") (class "Default")
      (node (ref "IC8") (pin "102") (pinfunction "PA10_102") (pintype "bidirectional"))
      (node (ref "JP11") (pin "3") (pinfunction "3_3") (pintype "passive"))
    )
    (net (code "112") (name "/USB_H_VBUS") (class "Default")
      (node (ref "IC8") (pin "101") (pinfunction "PA9_101") (pintype "bidirectional"))
      (node (ref "JP11") (pin "4") (pinfunction "4_4") (pintype "passive"))
    )
    (net (code "113") (name "/USB_ID") (class "Default")
      (node (ref "IC8") (pin "73") (pinfunction "PB12_73") (pintype "bidirectional"))
      (node (ref "JP7") (pin "1") (pinfunction "1_1") (pintype "passive"))
      (node (ref "USB") (pin "4") (pinfunction "ID_4") (pintype "bidirectional"))
    )
    (net (code "114") (name "/VBAT") (class "Default")
      (node (ref "IC8") (pin "6") (pinfunction "VBAT_6") (pintype "bidirectional"))
      (node (ref "JP15") (pin "1") (pinfunction "1_1") (pintype "passive"))
    )
    (net (code "115") (name "/VDDA") (class "Default")
      (node (ref "C24") (pin "1") (pinfunction "1_1") (pintype "passive"))
      (node (ref "C27") (pin "1") (pinfunction "1_1") (pintype "passive"))
      (node (ref "IC8") (pin "33") (pinfunction "VDDA_33") (pintype "bidirectional"))
      (node (ref "L4") (pin "1") (pinfunction "1_1") (pintype "passive"))
    )
    (net (code "116") (name "GND") (class "Default")
      (node (ref "C1") (pin "2") (pinfunction "2_2") (pintype "passive"))
      (node (ref "C10") (pin "2") (pinfunction "2_2") (pintype "passive"))
      (node (ref "C11") (pin "2") (pinfunction "2_2") (pintype "passive"))
      (node (ref "C110") (pin "1") (pinfunction "1_1") (pintype "passive"))
      (node (ref "C111") (pin "-") (pinfunction "-_-") (pintype "passive"))
      (node (ref "C112") (pin "2") (pinfunction "2_2") (pintype "passive"))
      (node (ref "C12") (pin "2") (pinfunction "2_2") (pintype "passive"))
      (node (ref "C15") (pin "2") (pinfunction "2_2") (pintype "passive"))
      (node (ref "C17") (pin "2") (pinfunction "2_2") (pintype "passive"))
      (node (ref "C18") (pin "2") (pinfunction "2_2") (pintype "passive"))
      (node (ref "C19") (pin "2") (pinfunction "2_2") (pintype "passive"))
      (node (ref "C2") (pin "2") (pinfunction "2_2") (pintype "passive"))
      (node (ref "C20") (pin "2") (pinfunction "2_2") (pintype "passive"))
      (node (ref "C24") (pin "2") (pinfunction "2_2") (pintype "passive"))
      (node (ref "C27") (pin "2") (pinfunction "2_2") (pintype "passive"))
      (node (ref "C3") (pin "2") (pinfunction "2_2") (pintype "passive"))
      (node (ref "C33") (pin "2") (pinfunction "2_2") (pintype "passive"))
      (node (ref "C34") (pin "2") (pinfunction "2_2") (pintype "passive"))
      (node (ref "C35") (pin "2") (pinfunction "2_2") (pintype "passive"))
      (node (ref "C37") (pin "2") (pinfunction "2_2") (pintype "passive"))
      (node (ref "C38") (pin "2") (pinfunction "2_2") (pintype "passive"))
      (node (ref "C39") (pin "2") (pinfunction "2_2") (pintype "passive"))
      (node (ref "C4") (pin "-") (pinfunction "-_-") (pintype "passive"))
      (node (ref "C40") (pin "2") (pinfunction "2_2") (pintype "passive"))
      (node (ref "C401") (pin "2") (pinfunction "2_2") (pintype "passive"))
      (node (ref "C402") (pin "2") (pinfunction "2_2") (pintype "passive"))
      (node (ref "C403") (pin "2") (pinfunction "2_2") (pintype "passive"))
      (node (ref "C404") (pin "2") (pinfunction "2_2") (pintype "passive"))
      (node (ref "C405") (pin "2") (pinfunction "2_2") (pintype "passive"))
      (node (ref "C406") (pin "2") (pinfunction "2_2") (pintype "passive"))
      (node (ref "C407") (pin "2") (pinfunction "2_2") (pintype "passive"))
      (node (ref "C408") (pin "2") (pinfunction "2_2") (pintype "passive"))
      (node (ref "C409") (pin "-") (pinfunction "-_-") (pintype "passive"))
      (node (ref "C41") (pin "2") (pinfunction "2_2") (pintype "passive"))
      (node (ref "C410") (pin "2") (pinfunction "2_2") (pintype "passive"))
      (node (ref "C411") (pin "2") (pinfunction "2_2") (pintype "passive"))
      (node (ref "C412") (pin "-") (pinfunction "-_-") (pintype "passive"))
      (node (ref "C42") (pin "2") (pinfunction "2_2") (pintype "passive"))
      (node (ref "C43") (pin "2") (pinfunction "2_2") (pintype "passive"))
      (node (ref "C5") (pin "2") (pinfunction "2_2") (pintype "passive"))
      (node (ref "C6") (pin "2") (pinfunction "2_2") (pintype "passive"))
      (node (ref "C7") (pin "2") (pinfunction "2_2") (pintype "passive"))
      (node (ref "C8") (pin "2") (pinfunction "2_2") (pintype "passive"))
      (node (ref "C9") (pin "2") (pinfunction "2_2") (pintype "passive"))
      (node (ref "C901") (pin "2") (pinfunction "2_2") (pintype "passive"))
      (node (ref "IC10") (pin "12") (pinfunction "GNDQ1_12") (pintype "bidirectional"))
      (node (ref "IC10") (pin "28") (pinfunction "GND1_28") (pintype "bidirectional"))
      (node (ref "IC10") (pin "41") (pinfunction "GND_41") (pintype "bidirectional"))
      (node (ref "IC10") (pin "46") (pinfunction "GNDQ2_46") (pintype "bidirectional"))
      (node (ref "IC10") (pin "52") (pinfunction "GNDQ3_52") (pintype "bidirectional"))
      (node (ref "IC10") (pin "54") (pinfunction "GND2_54") (pintype "bidirectional"))
      (node (ref "IC10") (pin "6") (pinfunction "GNDQ_6") (pintype "bidirectional"))
      (node (ref "IC2") (pin "2") (pinfunction "V-_2") (pintype "power_in"))
      (node (ref "IC4") (pin "21") (pinfunction "AGND_21") (pintype "bidirectional"))
      (node (ref "IC4") (pin "8") (pinfunction "DGND_8") (pintype "bidirectional"))
      (node (ref "IC8") (pin "107") (pinfunction "VSS6_107") (pintype "bidirectional"))
      (node (ref "IC8") (pin "120") (pinfunction "VSS7_120") (pintype "bidirectional"))
      (node (ref "IC8") (pin "130") (pinfunction "VSS8_130") (pintype "bidirectional"))
      (node (ref "IC8") (pin "143") (pinfunction "PDR_ON_143") (pintype "bidirectional"))
      (node (ref "IC8") (pin "16") (pinfunction "VSS_16") (pintype "bidirectional"))
      (node (ref "IC8") (pin "31") (pinfunction "VSSA_31") (pintype "bidirectional"))
      (node (ref "IC8") (pin "38") (pinfunction "VSS1_38") (pintype "bidirectional"))
      (node (ref "IC8") (pin "51") (pinfunction "VSS2_51") (pintype "bidirectional"))
      (node (ref "IC8") (pin "61") (pinfunction "VSS3_61") (pintype "bidirectional"))
      (node (ref "IC8") (pin "83") (pinfunction "VSS4_83") (pintype "bidirectional"))
      (node (ref "IC8") (pin "94") (pinfunction "VSS5_94") (pintype "bidirectional"))
      (node (ref "IC9") (pin "4") (pinfunction "VSS_4") (pintype "bidirectional"))
      (node (ref "JP2") (pin "2") (pinfunction "2_2") (pintype "passive"))
      (node (ref "JP4") (pin "3") (pinfunction "3_3") (pintype "passive"))
      (node (ref "JP5") (pin "2") (pinfunction "2_2") (pintype "passive"))
      (node (ref "JP6") (pin "6") (pinfunction "6_6") (pintype "passive"))
      (node (ref "JP7") (pin "5") (pinfunction "5_5") (pintype "passive"))
      (node (ref "L2") (pin "2") (pinfunction "2_2") (pintype "passive"))
      (node (ref "R3") (pin "1") (pinfunction "1_1") (pintype "passive"))
      (node (ref "R402") (pin "1") (pinfunction "1_1") (pintype "passive"))
      (node (ref "U4") (pin "2") (pinfunction "GND_2") (pintype "input"))
      (node (ref "X2") (pin "3") (pinfunction "S_3") (pintype "passive"))
    )
    (net (code "117") (name "Net-(IC4-FILT+)") (class "Default")
      (node (ref "C411") (pin "1") (pinfunction "1_1") (pintype "passive"))
      (node (ref "C412") (pin "+") (pinfunction "+_+") (pintype "passive"))
      (node (ref "IC4") (pin "22") (pinfunction "FILT+_22") (pintype "bidirectional"))
    )
    (net (code "118") (name "Net-(IC4-VA)") (class "Default")
      (node (ref "C407") (pin "1") (pinfunction "1_1") (pintype "passive"))
      (node (ref "C408") (pin "1") (pinfunction "1_1") (pintype "passive"))
      (node (ref "IC4") (pin "20") (pinfunction "VA_20") (pintype "bidirectional"))
      (node (ref "L3") (pin "2") (pinfunction "2_2") (pintype "passive"))
    )
    (net (code "119") (name "Net-(IC4-VD)") (class "Default")
      (node (ref "C405") (pin "1") (pinfunction "1_1") (pintype "passive"))
      (node (ref "C406") (pin "1") (pinfunction "1_1") (pintype "passive"))
      (node (ref "IC4") (pin "9") (pinfunction "VD_9") (pintype "bidirectional"))
      (node (ref "R401") (pin "1") (pinfunction "1_1") (pintype "passive"))
    )
    (net (code "120") (name "Net-(IC4-XTI)") (class "Default")
      (node (ref "C401") (pin "1") (pinfunction "1_1") (pintype "passive"))
      (node (ref "IC4") (pin "2") (pinfunction "XTI_2") (pintype "bidirectional"))
      (node (ref "Y1") (pin "2") (pinfunction "2_2") (pintype "passive"))
    )
    (net (code "121") (name "Net-(IC4-XTO)") (class "Default")
      (node (ref "C402") (pin "1") (pinfunction "1_1") (pintype "passive"))
      (node (ref "IC4") (pin "1") (pinfunction "XTO_1") (pintype "bidirectional"))
      (node (ref "Y1") (pin "1") (pinfunction "1_1") (pintype "passive"))
    )
    (net (code "122") (name "Net-(IC8A-PH0)") (class "Default")
      (node (ref "C11") (pin "1") (pinfunction "1_1") (pintype "passive"))
      (node (ref "IC8") (pin "23") (pinfunction "PH0_23") (pintype "bidirectional"))
      (node (ref "Y3") (pin "2") (pinfunction "2_2") (pintype "passive"))
    )
    (net (code "123") (name "Net-(IC8A-PH1)") (class "Default")
      (node (ref "C12") (pin "1") (pinfunction "1_1") (pintype "passive"))
      (node (ref "IC8") (pin "24") (pinfunction "PH1_24") (pintype "bidirectional"))
      (node (ref "Y3") (pin "1") (pinfunction "1_1") (pintype "passive"))
    )
    (net (code "124") (name "Net-(IC8B-VCAP_1)") (class "Default")
      (node (ref "C20") (pin "1") (pinfunction "1_1") (pintype "passive"))
      (node (ref "IC8") (pin "71") (pinfunction "VCAP_1_71") (pintype "bidirectional"))
    )
    (net (code "125") (name "Net-(IC8C-VCAP_2)") (class "Default")
      (node (ref "C19") (pin "1") (pinfunction "1_1") (pintype "passive"))
      (node (ref "IC8") (pin "106") (pinfunction "VCAP_2_106") (pintype "bidirectional"))
    )
    (net (code "126") (name "Net-(USB-D+)") (class "Default")
      (node (ref "R2") (pin "1") (pinfunction "1_1") (pintype "passive"))
      (node (ref "USB") (pin "3") (pinfunction "D+_3") (pintype "bidirectional"))
    )
    (net (code "127") (name "Net-(USB-D-)") (class "Default")
      (node (ref "R1") (pin "1") (pinfunction "1_1") (pintype "passive"))
      (node (ref "USB") (pin "2") (pinfunction "D-_2") (pintype "bidirectional"))
    )
    (net (code "128") (name "Net-(USB-GND)") (class "Default")
      (node (ref "L2") (pin "1") (pinfunction "1_1") (pintype "passive"))
      (node (ref "USB") (pin "5") (pinfunction "GND_5") (pintype "bidirectional"))
      (node (ref "USB") (pin "G") (pinfunction "SHIELD_G") (pintype "bidirectional"))
      (node (ref "USB") (pin "G2") (pinfunction "SHIELD_G2") (pintype "bidirectional"))
      (node (ref "USB") (pin "G3") (pinfunction "SHIELD_G3") (pintype "bidirectional"))
      (node (ref "USB") (pin "G4") (pinfunction "SHIELD_G4") (pintype "bidirectional"))
    )
    (net (code "129") (name "Net-(USB-VCC)") (class "Default")
      (node (ref "L1") (pin "2") (pinfunction "2_2") (pintype "passive"))
      (node (ref "USB") (pin "1") (pinfunction "VCC_1") (pintype "bidirectional"))
    )
    (net (code "130") (name "unconnected-(IC4-MCLK-Pad3)") (class "Default")
      (node (ref "IC4") (pin "3") (pinfunction "MCLK_3") (pintype "bidirectional"))
    )
    (net (code "131") (name "unconnected-(IC4-~{AMUTEC}-Pad23)") (class "Default")
      (node (ref "IC4") (pin "23") (pinfunction "~{AMUTEC}_23") (pintype "bidirectional"))
    )
    (net (code "132") (name "unconnected-(IC4-~{BMUTEC}-Pad28)") (class "Default")
      (node (ref "IC4") (pin "28") (pinfunction "~{BMUTEC}_28") (pintype "bidirectional"))
    )
    (net (code "133") (name "unconnected-(IC8A-PC15-Pad9)") (class "Default")
      (node (ref "IC8") (pin "9") (pinfunction "PC15_9") (pintype "bidirectional"))
    )
    (net (code "134") (name "unconnected-(IC8A-PF6-Pad18)") (class "Default")
      (node (ref "IC8") (pin "18") (pinfunction "PF6_18") (pintype "bidirectional"))
    )
    (net (code "135") (name "unconnected-(IC8B-PG2-Pad87)") (class "Default")
      (node (ref "IC8") (pin "87") (pinfunction "PG2_87") (pintype "bidirectional"))
    )
    (net (code "136") (name "unconnected-(IC8B-PG3-Pad88)") (class "Default")
      (node (ref "IC8") (pin "88") (pinfunction "PG3_88") (pintype "bidirectional"))
    )
    (net (code "137") (name "unconnected-(IC8B-PG6-Pad91)") (class "Default")
      (node (ref "IC8") (pin "91") (pinfunction "PG6_91") (pintype "bidirectional"))
    )
    (net (code "138") (name "unconnected-(IC8B-PG7-Pad92)") (class "Default")
      (node (ref "IC8") (pin "92") (pinfunction "PG7_92") (pintype "bidirectional"))
    )
    (net (code "139") (name "unconnected-(IC8C-PC7-Pad97)") (class "Default")
      (node (ref "IC8") (pin "97") (pinfunction "PC7_97") (pintype "bidirectional"))
    )
    (net (code "140") (name "unconnected-(IC8C-PD3-Pad117)") (class "Default")
      (node (ref "IC8") (pin "117") (pinfunction "PD3_117") (pintype "bidirectional"))
    )
    (net (code "141") (name "unconnected-(IC8C-PD4-Pad118)") (class "Default")
      (node (ref "IC8") (pin "118") (pinfunction "PD4_118") (pintype "bidirectional"))
    )
    (net (code "142") (name "unconnected-(IC8C-PD5-Pad119)") (class "Default")
      (node (ref "IC8") (pin "119") (pinfunction "PD5_119") (pintype "bidirectional"))
    )
    (net (code "143") (name "unconnected-(IC8C-PG10-Pad125)") (class "Default")
      (node (ref "IC8") (pin "125") (pinfunction "PG10_125") (pintype "bidirectional"))
    )
  )
)
